# mailbox.net
KiCad netlist of a schematic drawn in EAGLE
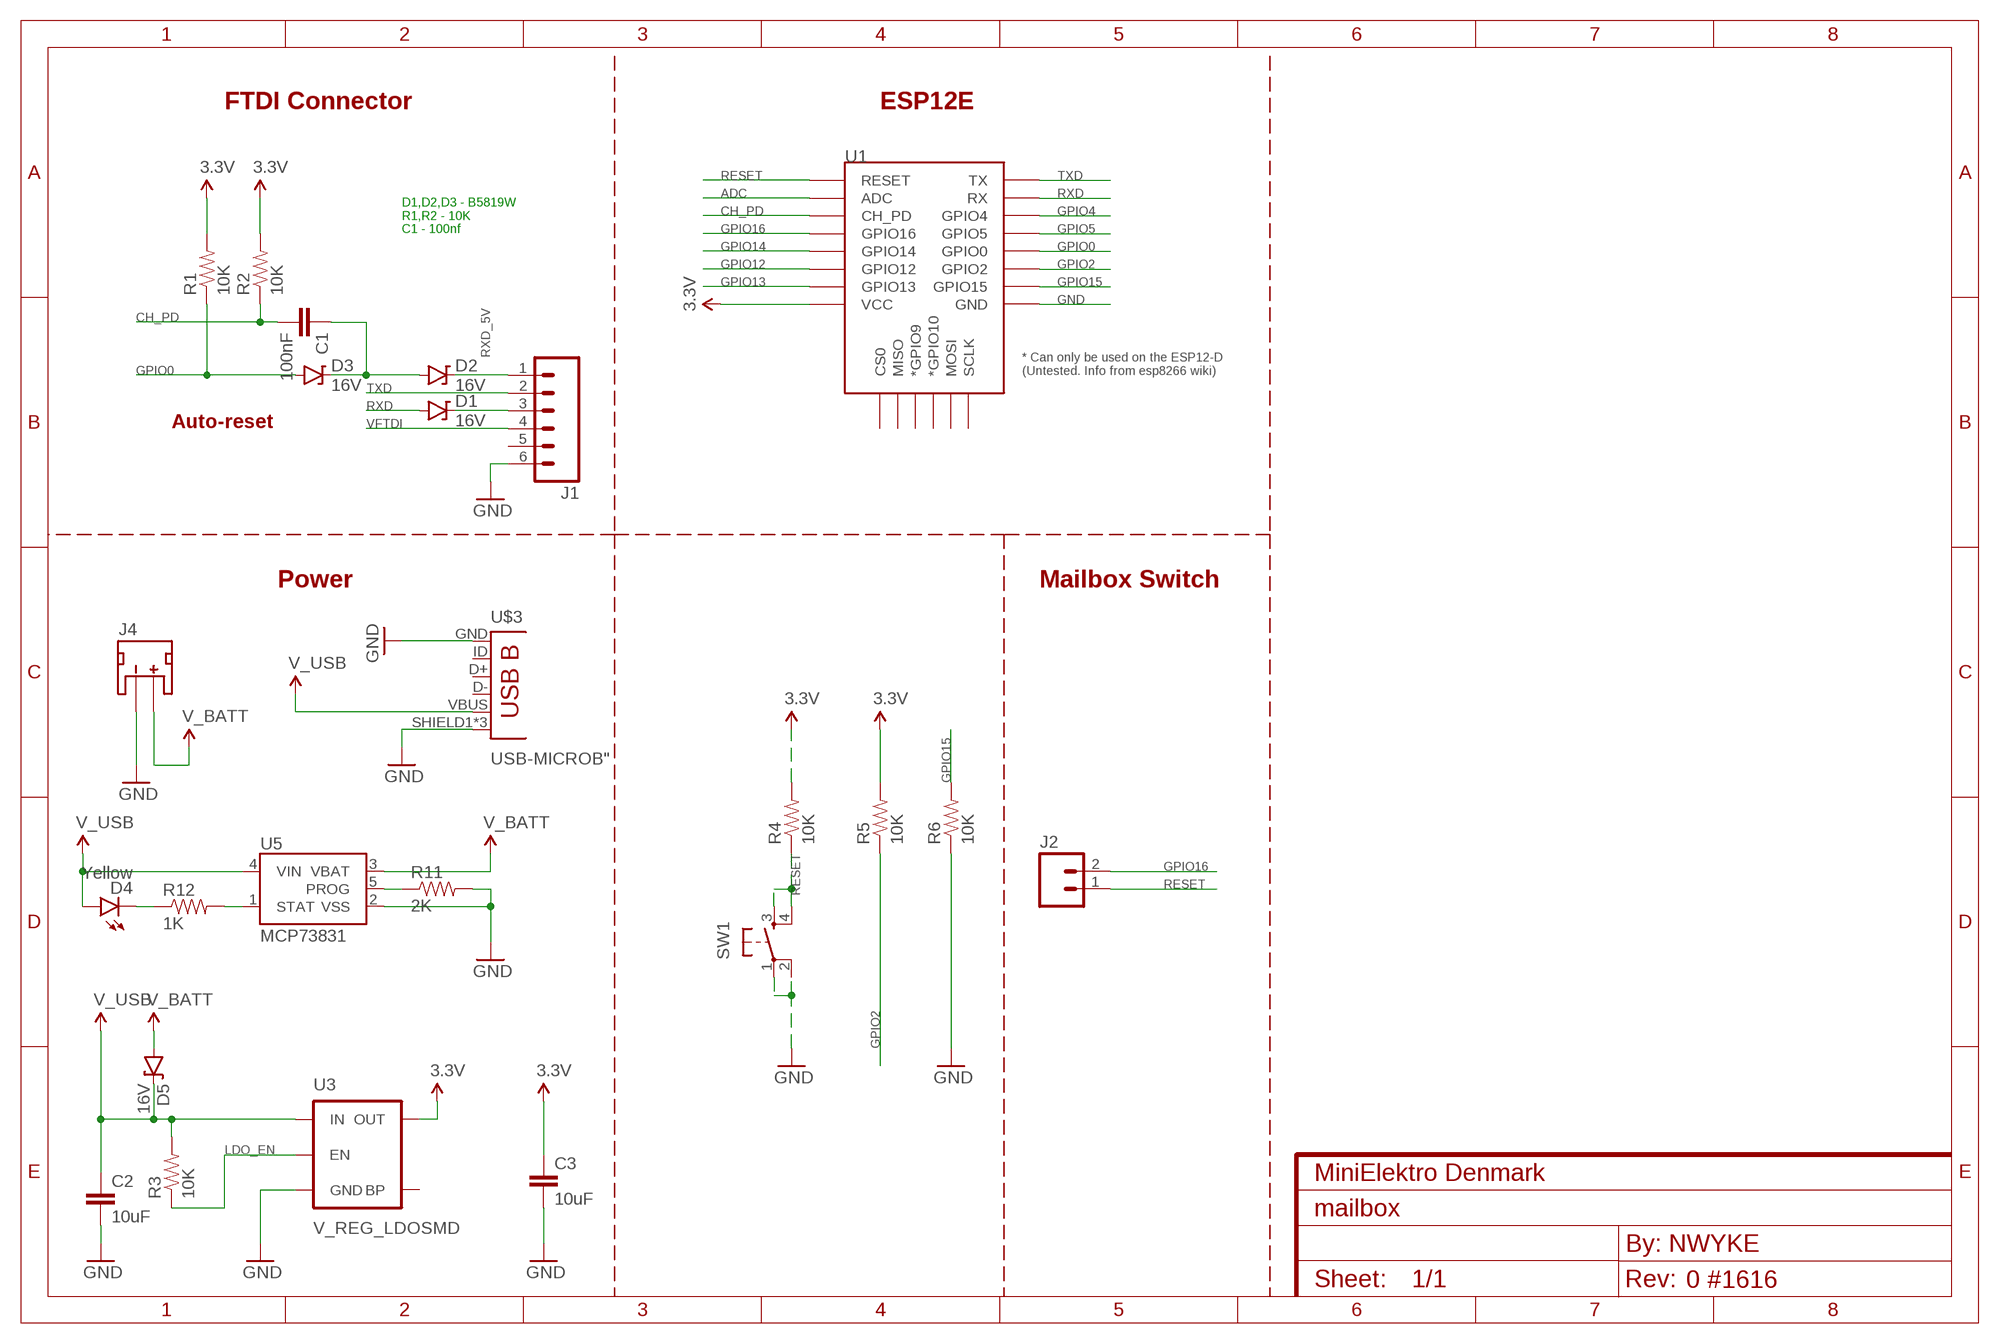
[diagram p0: schematic, sheet 1]

(export (version "E")
  (design (tool "Eeschema 10.0.6"))
  (components
    (comp (ref "C1")
      (value "100nF")
      (footprint "eagle-import:0402-CAP")
      (libsource (lib "eagle-import") (part "CAP0402-CAP"))
    )
    (comp (ref "C2")
      (value "10uF")
      (footprint "eagle-import:0402-CAP")
      (libsource (lib "eagle-import") (part "CAP0402-CAP"))
    )
    (comp (ref "C3")
      (value "10uF")
      (footprint "eagle-import:0402-CAP")
      (libsource (lib "eagle-import") (part "CAP0402-CAP"))
    )
    (comp (ref "D1")
      (value "16V")
      (footprint "eagle-import:SOD-123")
      (libsource (lib "eagle-import") (part "DIODE-ZENER16V"))
    )
    (comp (ref "D2")
      (value "16V")
      (footprint "eagle-import:SOD-123")
      (libsource (lib "eagle-import") (part "DIODE-ZENER16V"))
    )
    (comp (ref "D3")
      (value "16V")
      (footprint "eagle-import:SOD-123")
      (libsource (lib "eagle-import") (part "DIODE-ZENER16V"))
    )
    (comp (ref "D4")
      (value "Yellow")
      (footprint "eagle-import:LED-0603")
      (libsource (lib "eagle-import") (part "LED-YELLOW0603"))
    )
    (comp (ref "D5")
      (value "16V")
      (footprint "eagle-import:SOD-123")
      (libsource (lib "eagle-import") (part "DIODE-ZENER16V"))
    )
    (comp (ref "J1")
      (value "M06SILK_FEMALE_PTH")
      (footprint "eagle-import:1X06")
      (libsource (lib "eagle-import") (part "M06SILK_FEMALE_PTH"))
    )
    (comp (ref "J2")
      (value "M02LOCK")
      (footprint "eagle-import:1X02_LOCK")
      (libsource (lib "eagle-import") (part "M02LOCK"))
    )
    (comp (ref "J4")
      (value "JST_2MM_MALE")
      (footprint "eagle-import:JST-2-SMD")
      (libsource (lib "eagle-import") (part "JST_2MM_MALE"))
    )
    (comp (ref "R1")
      (value "10K")
      (footprint "eagle-import:0402-RES")
      (libsource (lib "eagle-import") (part "RESISTOR0402-RES"))
    )
    (comp (ref "R2")
      (value "10K")
      (footprint "eagle-import:0402-RES")
      (libsource (lib "eagle-import") (part "RESISTOR0402-RES"))
    )
    (comp (ref "R3")
      (value "10K")
      (footprint "eagle-import:0402-RES")
      (libsource (lib "eagle-import") (part "RESISTOR0402-RES"))
    )
    (comp (ref "R4")
      (value "10K")
      (footprint "eagle-import:0402-RES")
      (libsource (lib "eagle-import") (part "RESISTOR0402-RES"))
    )
    (comp (ref "R5")
      (value "10K")
      (footprint "eagle-import:0402-RES")
      (libsource (lib "eagle-import") (part "RESISTOR0402-RES"))
    )
    (comp (ref "R6")
      (value "10K")
      (footprint "eagle-import:0402-RES")
      (libsource (lib "eagle-import") (part "RESISTOR0402-RES"))
    )
    (comp (ref "R11")
      (value "2K")
      (footprint "eagle-import:0603-RES")
      (libsource (lib "eagle-import") (part "RESISTOR0603-RES"))
    )
    (comp (ref "R12")
      (value "1K")
      (footprint "eagle-import:0603-RES")
      (libsource (lib "eagle-import") (part "RESISTOR0603-RES"))
    )
    (comp (ref "SW1")
      (value "SWITCH_SPST_4_PINRECT")
      (footprint "eagle-import:TACTILE_SWITCH_SMD_4.6X2.8MM")
      (libsource (lib "eagle-import") (part "SWITCH_SPST_4_PINRECT"))
    )
    (comp (ref "U$3")
      (value "USB-MICROB\"")
      (footprint "eagle-import:USB-B-MICRO-SMD_V03")
      (libsource (lib "eagle-import") (part "USB-MICROB{dblquote}"))
    )
    (comp (ref "U1")
      (value "ESP12ESMD")
      (footprint "eagle-import:ESP12E-SMD")
      (libsource (lib "eagle-import") (part "ESP12ESMD"))
    )
    (comp (ref "U3")
      (value "V_REG_LDOSMD")
      (footprint "eagle-import:SOT23-5")
      (libsource (lib "eagle-import") (part "V_REG_LDOSMD"))
    )
    (comp (ref "U5")
      (value "MCP73831")
      (footprint "eagle-import:SOT23-5")
      (libsource (lib "eagle-import") (part "MCP73831"))
    )
  )
  (nets
    (net (code "1") (name "/ADC") (class "Default")
      (node (ref "U1") (pin "ADC") (pinfunction "ADC_ADC") (pintype "bidirectional"))
    )
    (net (code "2") (name "/CH_PD") (class "Default")
      (node (ref "C1") (pin "2") (pinfunction "2_2") (pintype "passive"))
      (node (ref "R2") (pin "1") (pinfunction "1_1") (pintype "passive"))
      (node (ref "U1") (pin "CH_PD") (pinfunction "CH_PD_CH_PD") (pintype "bidirectional"))
    )
    (net (code "3") (name "/GPIO0") (class "Default")
      (node (ref "D3") (pin "A") (pinfunction "A_A") (pintype "passive"))
      (node (ref "R1") (pin "1") (pinfunction "1_1") (pintype "passive"))
      (node (ref "U1") (pin "GPIO0") (pinfunction "GPIO0_GPIO0") (pintype "bidirectional"))
    )
    (net (code "4") (name "/GPIO2") (class "Default")
      (node (ref "R5") (pin "1") (pinfunction "1_1") (pintype "passive"))
      (node (ref "U1") (pin "GPIO2") (pinfunction "GPIO2_GPIO2") (pintype "bidirectional"))
    )
    (net (code "5") (name "/GPIO4") (class "Default")
      (node (ref "U1") (pin "GPIO4") (pinfunction "GPIO4_GPIO4") (pintype "bidirectional"))
    )
    (net (code "6") (name "/GPIO5") (class "Default")
      (node (ref "U1") (pin "GPIO5") (pinfunction "GPIO5_GPIO5") (pintype "bidirectional"))
    )
    (net (code "7") (name "/GPIO12") (class "Default")
      (node (ref "U1") (pin "GPIO12") (pinfunction "GPIO12_GPIO12") (pintype "bidirectional"))
    )
    (net (code "8") (name "/GPIO13") (class "Default")
      (node (ref "U1") (pin "GPIO13") (pinfunction "GPIO13_GPIO13") (pintype "bidirectional"))
    )
    (net (code "9") (name "/GPIO14") (class "Default")
      (node (ref "U1") (pin "GPIO14") (pinfunction "GPIO14_GPIO14") (pintype "bidirectional"))
    )
    (net (code "10") (name "/GPIO15") (class "Default")
      (node (ref "R6") (pin "2") (pinfunction "2_2") (pintype "passive"))
      (node (ref "U1") (pin "GPIO15") (pinfunction "GPIO15_GPIO15") (pintype "bidirectional"))
    )
    (net (code "11") (name "/GPIO16") (class "Default")
      (node (ref "J2") (pin "2") (pinfunction "2_2") (pintype "passive"))
      (node (ref "U1") (pin "GPIO16") (pinfunction "GPIO16_GPIO16") (pintype "bidirectional"))
    )
    (net (code "12") (name "/LDO_EN") (class "Default")
      (node (ref "R3") (pin "1") (pinfunction "1_1") (pintype "passive"))
      (node (ref "U3") (pin "3") (pinfunction "EN_3") (pintype "input"))
    )
    (net (code "13") (name "/RESET") (class "Default")
      (node (ref "J2") (pin "1") (pinfunction "1_1") (pintype "passive"))
      (node (ref "R4") (pin "1") (pinfunction "1_1") (pintype "passive"))
      (node (ref "SW1") (pin "3") (pinfunction "3_3") (pintype "passive"))
      (node (ref "SW1") (pin "4") (pinfunction "4_4") (pintype "passive"))
      (node (ref "U1") (pin "RESET") (pinfunction "RESET_RESET") (pintype "bidirectional"))
    )
    (net (code "14") (name "/RXD") (class "Default")
      (node (ref "D1") (pin "A") (pinfunction "A_A") (pintype "passive"))
      (node (ref "U1") (pin "RXD0") (pinfunction "RX_RXD0") (pintype "bidirectional"))
    )
    (net (code "15") (name "/RXD_5V") (class "Default")
      (node (ref "D1") (pin "C") (pinfunction "C_C") (pintype "passive"))
      (node (ref "J1") (pin "3") (pinfunction "3_3") (pintype "passive"))
    )
    (net (code "16") (name "/TXD") (class "Default")
      (node (ref "J1") (pin "2") (pinfunction "2_2") (pintype "passive"))
      (node (ref "U1") (pin "TXD0") (pinfunction "TX_TXD0") (pintype "bidirectional"))
    )
    (net (code "17") (name "/VFTDI") (class "Default")
      (node (ref "J1") (pin "4") (pinfunction "4_4") (pintype "passive"))
    )
    (net (code "18") (name "3.3V") (class "Default")
      (node (ref "C3") (pin "1") (pinfunction "1_1") (pintype "passive"))
      (node (ref "R1") (pin "2") (pinfunction "2_2") (pintype "passive"))
      (node (ref "R2") (pin "2") (pinfunction "2_2") (pintype "passive"))
      (node (ref "R4") (pin "2") (pinfunction "2_2") (pintype "passive"))
      (node (ref "R5") (pin "2") (pinfunction "2_2") (pintype "passive"))
      (node (ref "U1") (pin "VCC") (pinfunction "VCC_VCC") (pintype "bidirectional"))
      (node (ref "U3") (pin "5") (pinfunction "OUT_5") (pintype "passive"))
    )
    (net (code "19") (name "GND") (class "Default")
      (node (ref "C2") (pin "2") (pinfunction "2_2") (pintype "passive"))
      (node (ref "C3") (pin "2") (pinfunction "2_2") (pintype "passive"))
      (node (ref "J1") (pin "6") (pinfunction "6_6") (pintype "passive"))
      (node (ref "J4") (pin "1") (pinfunction "-_1") (pintype "bidirectional"))
      (node (ref "R11") (pin "2") (pinfunction "2_2") (pintype "passive"))
      (node (ref "R6") (pin "1") (pinfunction "1_1") (pintype "passive"))
      (node (ref "SW1") (pin "1") (pinfunction "1_1") (pintype "passive"))
      (node (ref "SW1") (pin "2") (pinfunction "2_2") (pintype "passive"))
      (node (ref "U$3") (pin "GND") (pinfunction "GND_GND") (pintype "bidirectional"))
      (node (ref "U$3") (pin "SHIELD1") (pinfunction "SHIELD_SHIELD1") (pintype "bidirectional"))
      (node (ref "U$3") (pin "SHIELD2") (pinfunction "SHIELD_SHIELD2") (pintype "bidirectional"))
      (node (ref "U$3") (pin "SHIELD3") (pinfunction "SHIELD_SHIELD3") (pintype "bidirectional"))
      (node (ref "U1") (pin "GND") (pinfunction "GND_GND") (pintype "bidirectional"))
      (node (ref "U3") (pin "2") (pinfunction "GND_2") (pintype "input"))
      (node (ref "U5") (pin "2") (pinfunction "VSS_2") (pintype "power_in"))
    )
    (net (code "20") (name "Net-(C1-Pad1)") (class "Default")
      (node (ref "C1") (pin "1") (pinfunction "1_1") (pintype "passive"))
      (node (ref "D2") (pin "A") (pinfunction "A_A") (pintype "passive"))
      (node (ref "D3") (pin "C") (pinfunction "C_C") (pintype "passive"))
    )
    (net (code "21") (name "Net-(D2-PadC)") (class "Default")
      (node (ref "D2") (pin "C") (pinfunction "C_C") (pintype "passive"))
      (node (ref "J1") (pin "1") (pinfunction "1_1") (pintype "passive"))
    )
    (net (code "22") (name "Net-(D4-PadC)") (class "Default")
      (node (ref "D4") (pin "C") (pinfunction "C_C") (pintype "passive"))
      (node (ref "R12") (pin "1") (pinfunction "1_1") (pintype "passive"))
    )
    (net (code "23") (name "Net-(U5-PROG)") (class "Default")
      (node (ref "R11") (pin "1") (pinfunction "1_1") (pintype "passive"))
      (node (ref "U5") (pin "5") (pinfunction "PROG_5") (pintype "input"))
    )
    (net (code "24") (name "Net-(U5-STAT)") (class "Default")
      (node (ref "R12") (pin "2") (pinfunction "2_2") (pintype "passive"))
      (node (ref "U5") (pin "1") (pinfunction "STAT_1") (pintype "output"))
    )
    (net (code "25") (name "V_BATT") (class "Default")
      (node (ref "D5") (pin "A") (pinfunction "A_A") (pintype "passive"))
      (node (ref "J4") (pin "2") (pinfunction "+_2") (pintype "bidirectional"))
      (node (ref "U5") (pin "3") (pinfunction "VBAT_3") (pintype "power_in"))
    )
    (net (code "26") (name "V_USB") (class "Default")
      (node (ref "C2") (pin "1") (pinfunction "1_1") (pintype "passive"))
      (node (ref "D4") (pin "A") (pinfunction "A_A") (pintype "passive"))
      (node (ref "D5") (pin "C") (pinfunction "C_C") (pintype "passive"))
      (node (ref "R3") (pin "2") (pinfunction "2_2") (pintype "passive"))
      (node (ref "U$3") (pin "VBUS") (pinfunction "VBUS_VBUS") (pintype "bidirectional"))
      (node (ref "U3") (pin "1") (pinfunction "IN_1") (pintype "input"))
      (node (ref "U5") (pin "4") (pinfunction "VIN_4") (pintype "power_in"))
    )
    (net (code "27") (name "unconnected-(J1-Pad5)") (class "Default")
      (node (ref "J1") (pin "5") (pinfunction "5_5") (pintype "passive"))
    )
    (net (code "28") (name "unconnected-(J4-PAD1-PadNC1)") (class "Default")
      (node (ref "J4") (pin "NC1") (pinfunction "PAD1_NC1") (pintype "bidirectional"))
    )
    (net (code "29") (name "unconnected-(J4-PAD2-PadNC2)") (class "Default")
      (node (ref "J4") (pin "NC2") (pinfunction "PAD2_NC2") (pintype "bidirectional"))
    )
    (net (code "30") (name "unconnected-(U$3-PadD+)") (class "Default")
      (node (ref "U$3") (pin "D+") (pinfunction "D+_D+") (pintype "bidirectional"))
    )
    (net (code "31") (name "unconnected-(U$3-PadD-)") (class "Default")
      (node (ref "U$3") (pin "D-") (pinfunction "D-_D-") (pintype "bidirectional"))
    )
    (net (code "32") (name "unconnected-(U$3-USBID-PadID)") (class "Default")
      (node (ref "U$3") (pin "ID") (pinfunction "USBID_ID") (pintype "bidirectional"))
    )
    (net (code "33") (name "unconnected-(U1-*GPIO9-PadGPIO9)") (class "Default")
      (node (ref "U1") (pin "GPIO9") (pinfunction "*GPIO9_GPIO9") (pintype "bidirectional"))
    )
    (net (code "34") (name "unconnected-(U1-*GPIO10-PadGPIO10)") (class "Default")
      (node (ref "U1") (pin "GPIO10") (pinfunction "*GPIO10_GPIO10") (pintype "bidirectional"))
    )
    (net (code "35") (name "unconnected-(U1-PadCS0)") (class "Default")
      (node (ref "U1") (pin "CS0") (pinfunction "CS0_CS0") (pintype "bidirectional"))
    )
    (net (code "36") (name "unconnected-(U1-PadMISO)") (class "Default")
      (node (ref "U1") (pin "MISO") (pinfunction "MISO_MISO") (pintype "bidirectional"))
    )
    (net (code "37") (name "unconnected-(U1-PadMOSI)") (class "Default")
      (node (ref "U1") (pin "MOSI") (pinfunction "MOSI_MOSI") (pintype "bidirectional"))
    )
    (net (code "38") (name "unconnected-(U1-PadSCLK)") (class "Default")
      (node (ref "U1") (pin "SCLK") (pinfunction "SCLK_SCLK") (pintype "bidirectional"))
    )
    (net (code "39") (name "unconnected-(U3-BP-Pad4)") (class "Default")
      (node (ref "U3") (pin "4") (pinfunction "BP_4") (pintype "input"))
    )
  )
)
